# Two_finger.net
KiCad netlist of a schematic drawn in Altium Designer
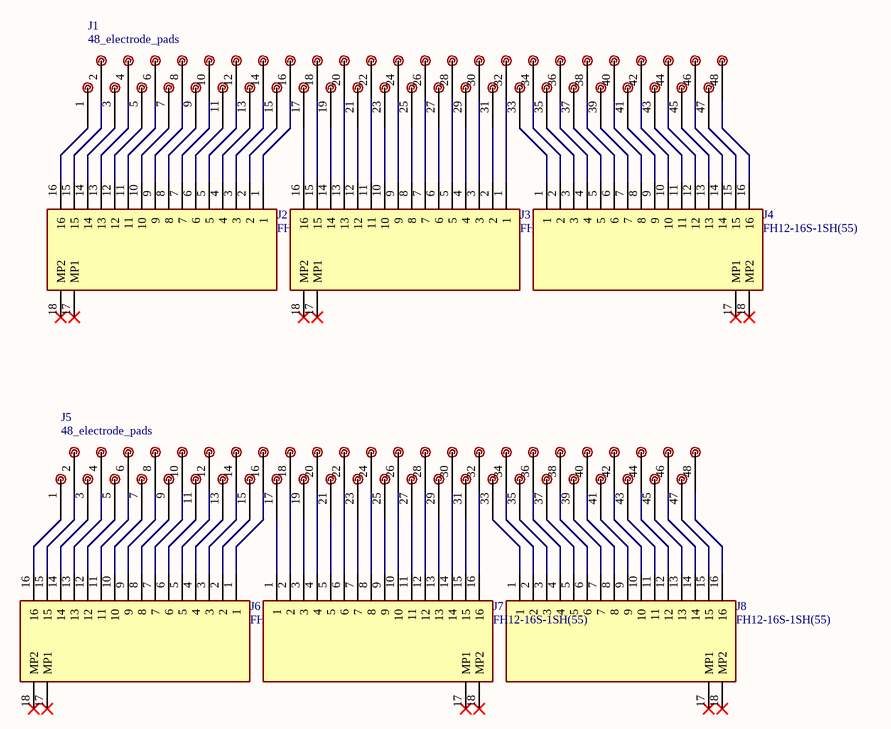
[diagram p0: Two_finger.SchDoc]

(export (version "E")
  (design (tool "Eeschema 10.0.6"))
  (components
    (comp (ref "J1")
      (value "48_electrode_pads")
      (footprint "48_ELECTRODE_PADS")
      (libsource (lib "48_pads") (part "48_electrode_pads"))
    )
    (comp (ref "J2")
      (value "FH12-16S-1SH(55)")
      (footprint "FH12-16S-1SH(55)")
      (libsource (lib "FH12-16S-1SH(55)") (part "FH12-16S-1SH(55)"))
    )
    (comp (ref "J3")
      (value "FH12-16S-1SH(55)")
      (footprint "FH12-16S-1SH(55)")
      (libsource (lib "FH12-16S-1SH(55)") (part "FH12-16S-1SH(55)"))
    )
    (comp (ref "J4")
      (value "FH12-16S-1SH(55)")
      (footprint "FH12-16S-1SH(55)")
      (libsource (lib "") (part "FH12-16S-1SH(55)_1"))
    )
    (comp (ref "J5")
      (value "48_electrode_pads")
      (footprint "48_ELECTRODE_PADS")
      (libsource (lib "48_pads") (part "48_electrode_pads"))
    )
    (comp (ref "J6")
      (value "FH12-16S-1SH(55)")
      (footprint "FH12-16S-1SH(55)")
      (libsource (lib "FH12-16S-1SH(55)") (part "FH12-16S-1SH(55)"))
    )
    (comp (ref "J7")
      (value "FH12-16S-1SH(55)")
      (footprint "FH12-16S-1SH(55)")
      (libsource (lib "") (part "FH12-16S-1SH(55)_1"))
    )
    (comp (ref "J8")
      (value "FH12-16S-1SH(55)")
      (footprint "FH12-16S-1SH(55)")
      (libsource (lib "") (part "FH12-16S-1SH(55)_1"))
    )
  )
  (nets
    (net (code "1") (name "Net-(J1-1-Pad2)") (class "Default")
      (node (ref "J1") (pin "2") (pinfunction "1_2") (pintype "passive"))
      (node (ref "J2") (pin "15") (pinfunction "15_15") (pintype "passive"))
    )
    (net (code "2") (name "Net-(J1-1-Pad3)") (class "Default")
      (node (ref "J1") (pin "3") (pinfunction "1_3") (pintype "passive"))
      (node (ref "J2") (pin "14") (pinfunction "14_14") (pintype "passive"))
    )
    (net (code "3") (name "Net-(J1-1-Pad4)") (class "Default")
      (node (ref "J1") (pin "4") (pinfunction "1_4") (pintype "passive"))
      (node (ref "J2") (pin "13") (pinfunction "13_13") (pintype "passive"))
    )
    (net (code "4") (name "Net-(J1-1-Pad5)") (class "Default")
      (node (ref "J1") (pin "5") (pinfunction "1_5") (pintype "passive"))
      (node (ref "J2") (pin "12") (pinfunction "12_12") (pintype "passive"))
    )
    (net (code "5") (name "Net-(J1-1-Pad6)") (class "Default")
      (node (ref "J1") (pin "6") (pinfunction "1_6") (pintype "passive"))
      (node (ref "J2") (pin "11") (pinfunction "11_11") (pintype "passive"))
    )
    (net (code "6") (name "Net-(J1-1-Pad7)") (class "Default")
      (node (ref "J1") (pin "7") (pinfunction "1_7") (pintype "passive"))
      (node (ref "J2") (pin "10") (pinfunction "10_10") (pintype "passive"))
    )
    (net (code "7") (name "Net-(J1-1-Pad8)") (class "Default")
      (node (ref "J1") (pin "8") (pinfunction "1_8") (pintype "passive"))
      (node (ref "J2") (pin "9") (pinfunction "9_9") (pintype "passive"))
    )
    (net (code "8") (name "Net-(J1-1-Pad9)") (class "Default")
      (node (ref "J1") (pin "9") (pinfunction "1_9") (pintype "passive"))
      (node (ref "J2") (pin "8") (pinfunction "8_8") (pintype "passive"))
    )
    (net (code "9") (name "Net-(J1-1-Pad10)") (class "Default")
      (node (ref "J1") (pin "10") (pinfunction "1_10") (pintype "passive"))
      (node (ref "J2") (pin "7") (pinfunction "7_7") (pintype "passive"))
    )
    (net (code "10") (name "Net-(J1-1-Pad11)") (class "Default")
      (node (ref "J1") (pin "11") (pinfunction "1_11") (pintype "passive"))
      (node (ref "J2") (pin "6") (pinfunction "6_6") (pintype "passive"))
    )
    (net (code "11") (name "Net-(J1-1-Pad12)") (class "Default")
      (node (ref "J1") (pin "12") (pinfunction "1_12") (pintype "passive"))
      (node (ref "J2") (pin "5") (pinfunction "5_5") (pintype "passive"))
    )
    (net (code "12") (name "Net-(J1-1-Pad13)") (class "Default")
      (node (ref "J1") (pin "13") (pinfunction "1_13") (pintype "passive"))
      (node (ref "J2") (pin "4") (pinfunction "4_4") (pintype "passive"))
    )
    (net (code "13") (name "Net-(J1-1-Pad14)") (class "Default")
      (node (ref "J1") (pin "14") (pinfunction "1_14") (pintype "passive"))
      (node (ref "J2") (pin "3") (pinfunction "3_3") (pintype "passive"))
    )
    (net (code "14") (name "Net-(J1-1-Pad15)") (class "Default")
      (node (ref "J1") (pin "15") (pinfunction "1_15") (pintype "passive"))
      (node (ref "J2") (pin "2") (pinfunction "2_2") (pintype "passive"))
    )
    (net (code "15") (name "Net-(J1-1-Pad16)") (class "Default")
      (node (ref "J1") (pin "16") (pinfunction "1_16") (pintype "passive"))
      (node (ref "J2") (pin "1") (pinfunction "1_1") (pintype "passive"))
    )
    (net (code "16") (name "Net-(J1-1-Pad17)") (class "Default")
      (node (ref "J1") (pin "17") (pinfunction "1_17") (pintype "passive"))
      (node (ref "J3") (pin "16") (pinfunction "16_16") (pintype "passive"))
    )
    (net (code "17") (name "Net-(J1-1-Pad18)") (class "Default")
      (node (ref "J1") (pin "18") (pinfunction "1_18") (pintype "passive"))
      (node (ref "J3") (pin "15") (pinfunction "15_15") (pintype "passive"))
    )
    (net (code "18") (name "Net-(J1-1-Pad19)") (class "Default")
      (node (ref "J1") (pin "19") (pinfunction "1_19") (pintype "passive"))
      (node (ref "J3") (pin "14") (pinfunction "14_14") (pintype "passive"))
    )
    (net (code "19") (name "Net-(J1-1-Pad20)") (class "Default")
      (node (ref "J1") (pin "20") (pinfunction "1_20") (pintype "passive"))
      (node (ref "J3") (pin "13") (pinfunction "13_13") (pintype "passive"))
    )
    (net (code "20") (name "Net-(J1-1-Pad21)") (class "Default")
      (node (ref "J1") (pin "21") (pinfunction "1_21") (pintype "passive"))
      (node (ref "J3") (pin "12") (pinfunction "12_12") (pintype "passive"))
    )
    (net (code "21") (name "Net-(J1-1-Pad22)") (class "Default")
      (node (ref "J1") (pin "22") (pinfunction "1_22") (pintype "passive"))
      (node (ref "J3") (pin "11") (pinfunction "11_11") (pintype "passive"))
    )
    (net (code "22") (name "Net-(J1-1-Pad23)") (class "Default")
      (node (ref "J1") (pin "23") (pinfunction "1_23") (pintype "passive"))
      (node (ref "J3") (pin "10") (pinfunction "10_10") (pintype "passive"))
    )
    (net (code "23") (name "Net-(J1-1-Pad24)") (class "Default")
      (node (ref "J1") (pin "24") (pinfunction "1_24") (pintype "passive"))
      (node (ref "J3") (pin "9") (pinfunction "9_9") (pintype "passive"))
    )
    (net (code "24") (name "Net-(J1-1-Pad25)") (class "Default")
      (node (ref "J1") (pin "25") (pinfunction "1_25") (pintype "passive"))
      (node (ref "J3") (pin "8") (pinfunction "8_8") (pintype "passive"))
    )
    (net (code "25") (name "Net-(J1-1-Pad26)") (class "Default")
      (node (ref "J1") (pin "26") (pinfunction "1_26") (pintype "passive"))
      (node (ref "J3") (pin "7") (pinfunction "7_7") (pintype "passive"))
    )
    (net (code "26") (name "Net-(J1-1-Pad27)") (class "Default")
      (node (ref "J1") (pin "27") (pinfunction "1_27") (pintype "passive"))
      (node (ref "J3") (pin "6") (pinfunction "6_6") (pintype "passive"))
    )
    (net (code "27") (name "Net-(J1-1-Pad28)") (class "Default")
      (node (ref "J1") (pin "28") (pinfunction "1_28") (pintype "passive"))
      (node (ref "J3") (pin "5") (pinfunction "5_5") (pintype "passive"))
    )
    (net (code "28") (name "Net-(J1-1-Pad29)") (class "Default")
      (node (ref "J1") (pin "29") (pinfunction "1_29") (pintype "passive"))
      (node (ref "J3") (pin "4") (pinfunction "4_4") (pintype "passive"))
    )
    (net (code "29") (name "Net-(J1-1-Pad30)") (class "Default")
      (node (ref "J1") (pin "30") (pinfunction "1_30") (pintype "passive"))
      (node (ref "J3") (pin "3") (pinfunction "3_3") (pintype "passive"))
    )
    (net (code "30") (name "Net-(J1-1-Pad32)") (class "Default")
      (node (ref "J1") (pin "32") (pinfunction "1_32") (pintype "passive"))
      (node (ref "J3") (pin "1") (pinfunction "1_1") (pintype "passive"))
    )
    (net (code "31") (name "Net-(J1-1-Pad33)") (class "Default")
      (node (ref "J1") (pin "33") (pinfunction "1_33") (pintype "passive"))
      (node (ref "J4") (pin "1") (pinfunction "1_1") (pintype "passive"))
    )
    (net (code "32") (name "Net-(J1-1-Pad34)") (class "Default")
      (node (ref "J1") (pin "34") (pinfunction "1_34") (pintype "passive"))
      (node (ref "J4") (pin "2") (pinfunction "2_2") (pintype "passive"))
    )
    (net (code "33") (name "Net-(J1-1-Pad35)") (class "Default")
      (node (ref "J1") (pin "35") (pinfunction "1_35") (pintype "passive"))
      (node (ref "J4") (pin "3") (pinfunction "3_3") (pintype "passive"))
    )
    (net (code "34") (name "Net-(J1-1-Pad36)") (class "Default")
      (node (ref "J1") (pin "36") (pinfunction "1_36") (pintype "passive"))
      (node (ref "J4") (pin "4") (pinfunction "4_4") (pintype "passive"))
    )
    (net (code "35") (name "Net-(J1-1-Pad37)") (class "Default")
      (node (ref "J1") (pin "37") (pinfunction "1_37") (pintype "passive"))
      (node (ref "J4") (pin "5") (pinfunction "5_5") (pintype "passive"))
    )
    (net (code "36") (name "Net-(J1-1-Pad38)") (class "Default")
      (node (ref "J1") (pin "38") (pinfunction "1_38") (pintype "passive"))
      (node (ref "J4") (pin "6") (pinfunction "6_6") (pintype "passive"))
    )
    (net (code "37") (name "Net-(J1-1-Pad39)") (class "Default")
      (node (ref "J1") (pin "39") (pinfunction "1_39") (pintype "passive"))
      (node (ref "J4") (pin "7") (pinfunction "7_7") (pintype "passive"))
    )
    (net (code "38") (name "Net-(J1-1-Pad40)") (class "Default")
      (node (ref "J1") (pin "40") (pinfunction "1_40") (pintype "passive"))
      (node (ref "J4") (pin "8") (pinfunction "8_8") (pintype "passive"))
    )
    (net (code "39") (name "Net-(J1-1-Pad41)") (class "Default")
      (node (ref "J1") (pin "41") (pinfunction "1_41") (pintype "passive"))
      (node (ref "J4") (pin "9") (pinfunction "9_9") (pintype "passive"))
    )
    (net (code "40") (name "Net-(J1-1-Pad42)") (class "Default")
      (node (ref "J1") (pin "42") (pinfunction "1_42") (pintype "passive"))
      (node (ref "J4") (pin "10") (pinfunction "10_10") (pintype "passive"))
    )
    (net (code "41") (name "Net-(J1-1-Pad43)") (class "Default")
      (node (ref "J1") (pin "43") (pinfunction "1_43") (pintype "passive"))
      (node (ref "J4") (pin "11") (pinfunction "11_11") (pintype "passive"))
    )
    (net (code "42") (name "Net-(J1-1-Pad44)") (class "Default")
      (node (ref "J1") (pin "44") (pinfunction "1_44") (pintype "passive"))
      (node (ref "J4") (pin "12") (pinfunction "12_12") (pintype "passive"))
    )
    (net (code "43") (name "Net-(J1-1-Pad45)") (class "Default")
      (node (ref "J1") (pin "45") (pinfunction "1_45") (pintype "passive"))
      (node (ref "J4") (pin "13") (pinfunction "13_13") (pintype "passive"))
    )
    (net (code "44") (name "Net-(J1-1-Pad46)") (class "Default")
      (node (ref "J1") (pin "46") (pinfunction "1_46") (pintype "passive"))
      (node (ref "J4") (pin "14") (pinfunction "14_14") (pintype "passive"))
    )
    (net (code "45") (name "Net-(J1-1-Pad47)") (class "Default")
      (node (ref "J1") (pin "47") (pinfunction "1_47") (pintype "passive"))
      (node (ref "J4") (pin "15") (pinfunction "15_15") (pintype "passive"))
    )
    (net (code "46") (name "Net-(J1-1-Pad48)") (class "Default")
      (node (ref "J1") (pin "48") (pinfunction "1_48") (pintype "passive"))
      (node (ref "J4") (pin "16") (pinfunction "16_16") (pintype "passive"))
    )
    (net (code "47") (name "Net-(J1-Pad1)") (class "Default")
      (node (ref "J1") (pin "1") (pinfunction "1_1") (pintype "passive"))
      (node (ref "J2") (pin "16") (pinfunction "16_16") (pintype "passive"))
    )
    (net (code "48") (name "Net-(J1-Pad31)") (class "Default")
      (node (ref "J1") (pin "31") (pinfunction "31_31") (pintype "passive"))
      (node (ref "J3") (pin "2") (pinfunction "2_2") (pintype "passive"))
    )
    (net (code "49") (name "Net-(J5-1-Pad2)") (class "Default")
      (node (ref "J5") (pin "2") (pinfunction "1_2") (pintype "passive"))
      (node (ref "J6") (pin "15") (pinfunction "15_15") (pintype "passive"))
    )
    (net (code "50") (name "Net-(J5-1-Pad3)") (class "Default")
      (node (ref "J5") (pin "3") (pinfunction "1_3") (pintype "passive"))
      (node (ref "J6") (pin "14") (pinfunction "14_14") (pintype "passive"))
    )
    (net (code "51") (name "Net-(J5-1-Pad4)") (class "Default")
      (node (ref "J5") (pin "4") (pinfunction "1_4") (pintype "passive"))
      (node (ref "J6") (pin "13") (pinfunction "13_13") (pintype "passive"))
    )
    (net (code "52") (name "Net-(J5-1-Pad5)") (class "Default")
      (node (ref "J5") (pin "5") (pinfunction "1_5") (pintype "passive"))
      (node (ref "J6") (pin "12") (pinfunction "12_12") (pintype "passive"))
    )
    (net (code "53") (name "Net-(J5-1-Pad6)") (class "Default")
      (node (ref "J5") (pin "6") (pinfunction "1_6") (pintype "passive"))
      (node (ref "J6") (pin "11") (pinfunction "11_11") (pintype "passive"))
    )
    (net (code "54") (name "Net-(J5-1-Pad7)") (class "Default")
      (node (ref "J5") (pin "7") (pinfunction "1_7") (pintype "passive"))
      (node (ref "J6") (pin "10") (pinfunction "10_10") (pintype "passive"))
    )
    (net (code "55") (name "Net-(J5-1-Pad8)") (class "Default")
      (node (ref "J5") (pin "8") (pinfunction "1_8") (pintype "passive"))
      (node (ref "J6") (pin "9") (pinfunction "9_9") (pintype "passive"))
    )
    (net (code "56") (name "Net-(J5-1-Pad9)") (class "Default")
      (node (ref "J5") (pin "9") (pinfunction "1_9") (pintype "passive"))
      (node (ref "J6") (pin "8") (pinfunction "8_8") (pintype "passive"))
    )
    (net (code "57") (name "Net-(J5-1-Pad10)") (class "Default")
      (node (ref "J5") (pin "10") (pinfunction "1_10") (pintype "passive"))
      (node (ref "J6") (pin "7") (pinfunction "7_7") (pintype "passive"))
    )
    (net (code "58") (name "Net-(J5-1-Pad11)") (class "Default")
      (node (ref "J5") (pin "11") (pinfunction "1_11") (pintype "passive"))
      (node (ref "J6") (pin "6") (pinfunction "6_6") (pintype "passive"))
    )
    (net (code "59") (name "Net-(J5-1-Pad12)") (class "Default")
      (node (ref "J5") (pin "12") (pinfunction "1_12") (pintype "passive"))
      (node (ref "J6") (pin "5") (pinfunction "5_5") (pintype "passive"))
    )
    (net (code "60") (name "Net-(J5-1-Pad13)") (class "Default")
      (node (ref "J5") (pin "13") (pinfunction "1_13") (pintype "passive"))
      (node (ref "J6") (pin "4") (pinfunction "4_4") (pintype "passive"))
    )
    (net (code "61") (name "Net-(J5-1-Pad14)") (class "Default")
      (node (ref "J5") (pin "14") (pinfunction "1_14") (pintype "passive"))
      (node (ref "J6") (pin "3") (pinfunction "3_3") (pintype "passive"))
    )
    (net (code "62") (name "Net-(J5-1-Pad15)") (class "Default")
      (node (ref "J5") (pin "15") (pinfunction "1_15") (pintype "passive"))
      (node (ref "J6") (pin "2") (pinfunction "2_2") (pintype "passive"))
    )
    (net (code "63") (name "Net-(J5-1-Pad16)") (class "Default")
      (node (ref "J5") (pin "16") (pinfunction "1_16") (pintype "passive"))
      (node (ref "J6") (pin "1") (pinfunction "1_1") (pintype "passive"))
    )
    (net (code "64") (name "Net-(J5-1-Pad17)") (class "Default")
      (node (ref "J5") (pin "17") (pinfunction "1_17") (pintype "passive"))
      (node (ref "J7") (pin "1") (pinfunction "1_1") (pintype "passive"))
    )
    (net (code "65") (name "Net-(J5-1-Pad18)") (class "Default")
      (node (ref "J5") (pin "18") (pinfunction "1_18") (pintype "passive"))
      (node (ref "J7") (pin "2") (pinfunction "2_2") (pintype "passive"))
    )
    (net (code "66") (name "Net-(J5-1-Pad19)") (class "Default")
      (node (ref "J5") (pin "19") (pinfunction "1_19") (pintype "passive"))
      (node (ref "J7") (pin "3") (pinfunction "3_3") (pintype "passive"))
    )
    (net (code "67") (name "Net-(J5-1-Pad20)") (class "Default")
      (node (ref "J5") (pin "20") (pinfunction "1_20") (pintype "passive"))
      (node (ref "J7") (pin "4") (pinfunction "4_4") (pintype "passive"))
    )
    (net (code "68") (name "Net-(J5-1-Pad21)") (class "Default")
      (node (ref "J5") (pin "21") (pinfunction "1_21") (pintype "passive"))
      (node (ref "J7") (pin "5") (pinfunction "5_5") (pintype "passive"))
    )
    (net (code "69") (name "Net-(J5-1-Pad22)") (class "Default")
      (node (ref "J5") (pin "22") (pinfunction "1_22") (pintype "passive"))
      (node (ref "J7") (pin "6") (pinfunction "6_6") (pintype "passive"))
    )
    (net (code "70") (name "Net-(J5-1-Pad23)") (class "Default")
      (node (ref "J5") (pin "23") (pinfunction "1_23") (pintype "passive"))
      (node (ref "J7") (pin "7") (pinfunction "7_7") (pintype "passive"))
    )
    (net (code "71") (name "Net-(J5-1-Pad24)") (class "Default")
      (node (ref "J5") (pin "24") (pinfunction "1_24") (pintype "passive"))
      (node (ref "J7") (pin "8") (pinfunction "8_8") (pintype "passive"))
    )
    (net (code "72") (name "Net-(J5-1-Pad25)") (class "Default")
      (node (ref "J5") (pin "25") (pinfunction "1_25") (pintype "passive"))
      (node (ref "J7") (pin "9") (pinfunction "9_9") (pintype "passive"))
    )
    (net (code "73") (name "Net-(J5-1-Pad26)") (class "Default")
      (node (ref "J5") (pin "26") (pinfunction "1_26") (pintype "passive"))
      (node (ref "J7") (pin "10") (pinfunction "10_10") (pintype "passive"))
    )
    (net (code "74") (name "Net-(J5-1-Pad27)") (class "Default")
      (node (ref "J5") (pin "27") (pinfunction "1_27") (pintype "passive"))
      (node (ref "J7") (pin "11") (pinfunction "11_11") (pintype "passive"))
    )
    (net (code "75") (name "Net-(J5-1-Pad28)") (class "Default")
      (node (ref "J5") (pin "28") (pinfunction "1_28") (pintype "passive"))
      (node (ref "J7") (pin "12") (pinfunction "12_12") (pintype "passive"))
    )
    (net (code "76") (name "Net-(J5-1-Pad29)") (class "Default")
      (node (ref "J5") (pin "29") (pinfunction "1_29") (pintype "passive"))
      (node (ref "J7") (pin "13") (pinfunction "13_13") (pintype "passive"))
    )
    (net (code "77") (name "Net-(J5-1-Pad30)") (class "Default")
      (node (ref "J5") (pin "30") (pinfunction "1_30") (pintype "passive"))
      (node (ref "J7") (pin "14") (pinfunction "14_14") (pintype "passive"))
    )
    (net (code "78") (name "Net-(J5-1-Pad32)") (class "Default")
      (node (ref "J5") (pin "32") (pinfunction "1_32") (pintype "passive"))
      (node (ref "J7") (pin "16") (pinfunction "16_16") (pintype "passive"))
    )
    (net (code "79") (name "Net-(J5-1-Pad33)") (class "Default")
      (node (ref "J5") (pin "33") (pinfunction "1_33") (pintype "passive"))
      (node (ref "J8") (pin "1") (pinfunction "1_1") (pintype "passive"))
    )
    (net (code "80") (name "Net-(J5-1-Pad34)") (class "Default")
      (node (ref "J5") (pin "34") (pinfunction "1_34") (pintype "passive"))
      (node (ref "J8") (pin "2") (pinfunction "2_2") (pintype "passive"))
    )
    (net (code "81") (name "Net-(J5-1-Pad35)") (class "Default")
      (node (ref "J5") (pin "35") (pinfunction "1_35") (pintype "passive"))
      (node (ref "J8") (pin "3") (pinfunction "3_3") (pintype "passive"))
    )
    (net (code "82") (name "Net-(J5-1-Pad36)") (class "Default")
      (node (ref "J5") (pin "36") (pinfunction "1_36") (pintype "passive"))
      (node (ref "J8") (pin "4") (pinfunction "4_4") (pintype "passive"))
    )
    (net (code "83") (name "Net-(J5-1-Pad37)") (class "Default")
      (node (ref "J5") (pin "37") (pinfunction "1_37") (pintype "passive"))
      (node (ref "J8") (pin "5") (pinfunction "5_5") (pintype "passive"))
    )
    (net (code "84") (name "Net-(J5-1-Pad38)") (class "Default")
      (node (ref "J5") (pin "38") (pinfunction "1_38") (pintype "passive"))
      (node (ref "J8") (pin "6") (pinfunction "6_6") (pintype "passive"))
    )
    (net (code "85") (name "Net-(J5-1-Pad39)") (class "Default")
      (node (ref "J5") (pin "39") (pinfunction "1_39") (pintype "passive"))
      (node (ref "J8") (pin "7") (pinfunction "7_7") (pintype "passive"))
    )
    (net (code "86") (name "Net-(J5-1-Pad40)") (class "Default")
      (node (ref "J5") (pin "40") (pinfunction "1_40") (pintype "passive"))
      (node (ref "J8") (pin "8") (pinfunction "8_8") (pintype "passive"))
    )
    (net (code "87") (name "Net-(J5-1-Pad41)") (class "Default")
      (node (ref "J5") (pin "41") (pinfunction "1_41") (pintype "passive"))
      (node (ref "J8") (pin "9") (pinfunction "9_9") (pintype "passive"))
    )
    (net (code "88") (name "Net-(J5-1-Pad42)") (class "Default")
      (node (ref "J5") (pin "42") (pinfunction "1_42") (pintype "passive"))
      (node (ref "J8") (pin "10") (pinfunction "10_10") (pintype "passive"))
    )
    (net (code "89") (name "Net-(J5-1-Pad43)") (class "Default")
      (node (ref "J5") (pin "43") (pinfunction "1_43") (pintype "passive"))
      (node (ref "J8") (pin "11") (pinfunction "11_11") (pintype "passive"))
    )
    (net (code "90") (name "Net-(J5-1-Pad44)") (class "Default")
      (node (ref "J5") (pin "44") (pinfunction "1_44") (pintype "passive"))
      (node (ref "J8") (pin "12") (pinfunction "12_12") (pintype "passive"))
    )
    (net (code "91") (name "Net-(J5-1-Pad45)") (class "Default")
      (node (ref "J5") (pin "45") (pinfunction "1_45") (pintype "passive"))
      (node (ref "J8") (pin "13") (pinfunction "13_13") (pintype "passive"))
    )
    (net (code "92") (name "Net-(J5-1-Pad46)") (class "Default")
      (node (ref "J5") (pin "46") (pinfunction "1_46") (pintype "passive"))
      (node (ref "J8") (pin "14") (pinfunction "14_14") (pintype "passive"))
    )
    (net (code "93") (name "Net-(J5-1-Pad47)") (class "Default")
      (node (ref "J5") (pin "47") (pinfunction "1_47") (pintype "passive"))
      (node (ref "J8") (pin "15") (pinfunction "15_15") (pintype "passive"))
    )
    (net (code "94") (name "Net-(J5-1-Pad48)") (class "Default")
      (node (ref "J5") (pin "48") (pinfunction "1_48") (pintype "passive"))
      (node (ref "J8") (pin "16") (pinfunction "16_16") (pintype "passive"))
    )
    (net (code "95") (name "Net-(J5-Pad1)") (class "Default")
      (node (ref "J5") (pin "1") (pinfunction "1_1") (pintype "passive"))
      (node (ref "J6") (pin "16") (pinfunction "16_16") (pintype "passive"))
    )
    (net (code "96") (name "Net-(J5-Pad31)") (class "Default")
      (node (ref "J5") (pin "31") (pinfunction "31_31") (pintype "passive"))
      (node (ref "J7") (pin "15") (pinfunction "15_15") (pintype "passive"))
    )
    (net (code "97") (name "unconnected-(J2-MP1-Pad17)") (class "Default")
      (node (ref "J2") (pin "17") (pinfunction "MP1_17") (pintype "passive+no_connect"))
    )
    (net (code "98") (name "unconnected-(J2-MP2-Pad18)") (class "Default")
      (node (ref "J2") (pin "18") (pinfunction "MP2_18") (pintype "passive+no_connect"))
    )
    (net (code "99") (name "unconnected-(J3-MP1-Pad17)") (class "Default")
      (node (ref "J3") (pin "17") (pinfunction "MP1_17") (pintype "passive+no_connect"))
    )
    (net (code "100") (name "unconnected-(J3-MP2-Pad18)") (class "Default")
      (node (ref "J3") (pin "18") (pinfunction "MP2_18") (pintype "passive+no_connect"))
    )
    (net (code "101") (name "unconnected-(J4-MP1-Pad17)") (class "Default")
      (node (ref "J4") (pin "17") (pinfunction "MP1_17") (pintype "passive+no_connect"))
    )
    (net (code "102") (name "unconnected-(J4-MP2-Pad18)") (class "Default")
      (node (ref "J4") (pin "18") (pinfunction "MP2_18") (pintype "passive+no_connect"))
    )
    (net (code "103") (name "unconnected-(J6-MP1-Pad17)") (class "Default")
      (node (ref "J6") (pin "17") (pinfunction "MP1_17") (pintype "passive+no_connect"))
    )
    (net (code "104") (name "unconnected-(J6-MP2-Pad18)") (class "Default")
      (node (ref "J6") (pin "18") (pinfunction "MP2_18") (pintype "passive+no_connect"))
    )
    (net (code "105") (name "unconnected-(J7-MP1-Pad17)") (class "Default")
      (node (ref "J7") (pin "17") (pinfunction "MP1_17") (pintype "passive+no_connect"))
    )
    (net (code "106") (name "unconnected-(J7-MP2-Pad18)") (class "Default")
      (node (ref "J7") (pin "18") (pinfunction "MP2_18") (pintype "passive+no_connect"))
    )
    (net (code "107") (name "unconnected-(J8-MP1-Pad17)") (class "Default")
      (node (ref "J8") (pin "17") (pinfunction "MP1_17") (pintype "passive+no_connect"))
    )
    (net (code "108") (name "unconnected-(J8-MP2-Pad18)") (class "Default")
      (node (ref "J8") (pin "18") (pinfunction "MP2_18") (pintype "passive+no_connect"))
    )
  )
)
